# Motors_Drivers.net
KiCad netlist of a schematic drawn in Altium Designer
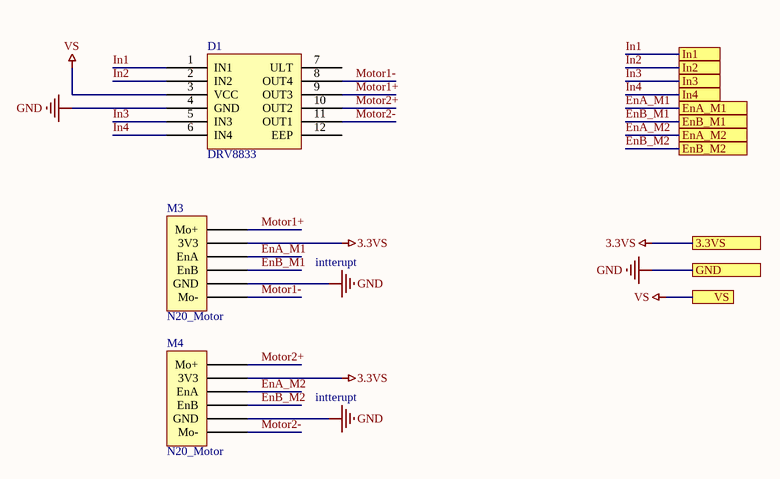
[diagram p0: Motors&Drivers.SchDoc]

(export (version "E")
  (design (tool "Eeschema 10.0.6"))
  (components
    (comp (ref "D1")
      (value "DRV8833")
      (footprint "DRV8833")
      (description "Module")
      (libsource (lib "MicroMouse") (part "DRV8833"))
    )
    (comp (ref "M3")
      (value "N20_Motor")
      (footprint "Header_N20_Motor")
      (libsource (lib "MicroMouse") (part "N20_Motor"))
    )
    (comp (ref "M4")
      (value "N20_Motor")
      (footprint "Header_N20_Motor")
      (libsource (lib "MicroMouse") (part "N20_Motor"))
    )
  )
  (nets
    (net (code "1") (name "/EnA_M1") (class "Default")
      (node (ref "M3") (pin "EnA") (pinfunction "EnA_EnA") (pintype "passive"))
    )
    (net (code "2") (name "/EnA_M2") (class "Default")
      (node (ref "M4") (pin "EnA") (pinfunction "EnA_EnA") (pintype "passive"))
    )
    (net (code "3") (name "/EnB_M1") (class "Default")
      (node (ref "M3") (pin "EnB") (pinfunction "EnB_EnB") (pintype "passive"))
    )
    (net (code "4") (name "/EnB_M2") (class "Default")
      (node (ref "M4") (pin "EnB") (pinfunction "EnB_EnB") (pintype "passive"))
    )
    (net (code "5") (name "/In1") (class "Default")
      (node (ref "D1") (pin "1") (pinfunction "IN1_1") (pintype "passive"))
    )
    (net (code "6") (name "/In2") (class "Default")
      (node (ref "D1") (pin "2") (pinfunction "IN2_2") (pintype "passive"))
    )
    (net (code "7") (name "/In3") (class "Default")
      (node (ref "D1") (pin "5") (pinfunction "IN3_5") (pintype "passive"))
    )
    (net (code "8") (name "/In4") (class "Default")
      (node (ref "D1") (pin "6") (pinfunction "IN4_6") (pintype "passive"))
    )
    (net (code "9") (name "/Motor1+") (class "Default")
      (node (ref "D1") (pin "9") (pinfunction "OUT3_9") (pintype "passive"))
      (node (ref "M3") (pin "Mo+") (pinfunction "Mo+_Mo+") (pintype "passive"))
    )
    (net (code "10") (name "/Motor1-") (class "Default")
      (node (ref "D1") (pin "8") (pinfunction "OUT4_8") (pintype "passive"))
      (node (ref "M3") (pin "Mo-") (pinfunction "Mo-_Mo-") (pintype "passive"))
    )
    (net (code "11") (name "/Motor2+") (class "Default")
      (node (ref "D1") (pin "10") (pinfunction "OUT2_10") (pintype "passive"))
      (node (ref "M4") (pin "Mo+") (pinfunction "Mo+_Mo+") (pintype "passive"))
    )
    (net (code "12") (name "/Motor2-") (class "Default")
      (node (ref "D1") (pin "11") (pinfunction "OUT1_11") (pintype "passive"))
      (node (ref "M4") (pin "Mo-") (pinfunction "Mo-_Mo-") (pintype "passive"))
    )
    (net (code "13") (name "3.3VS") (class "Default")
      (node (ref "M3") (pin "3V3") (pinfunction "3V3_3V3") (pintype "passive"))
      (node (ref "M4") (pin "3V3") (pinfunction "3V3_3V3") (pintype "passive"))
    )
    (net (code "14") (name "GND") (class "Default")
      (node (ref "D1") (pin "4") (pinfunction "GND_4") (pintype "passive"))
      (node (ref "M3") (pin "GND") (pinfunction "GND_GND") (pintype "passive"))
      (node (ref "M4") (pin "GND") (pinfunction "GND_GND") (pintype "passive"))
    )
    (net (code "15") (name "VS") (class "Default")
      (node (ref "D1") (pin "3") (pinfunction "VCC_3") (pintype "passive"))
    )
    (net (code "16") (name "unconnected-(D1-EEP-Pad12)") (class "Default")
      (node (ref "D1") (pin "12") (pinfunction "EEP_12") (pintype "passive"))
    )
    (net (code "17") (name "unconnected-(D1-ULT-Pad7)") (class "Default")
      (node (ref "D1") (pin "7") (pinfunction "ULT_7") (pintype "passive"))
    )
  )
)
